# Serial_LCD.net
KiCad netlist of a schematic drawn in EAGLE
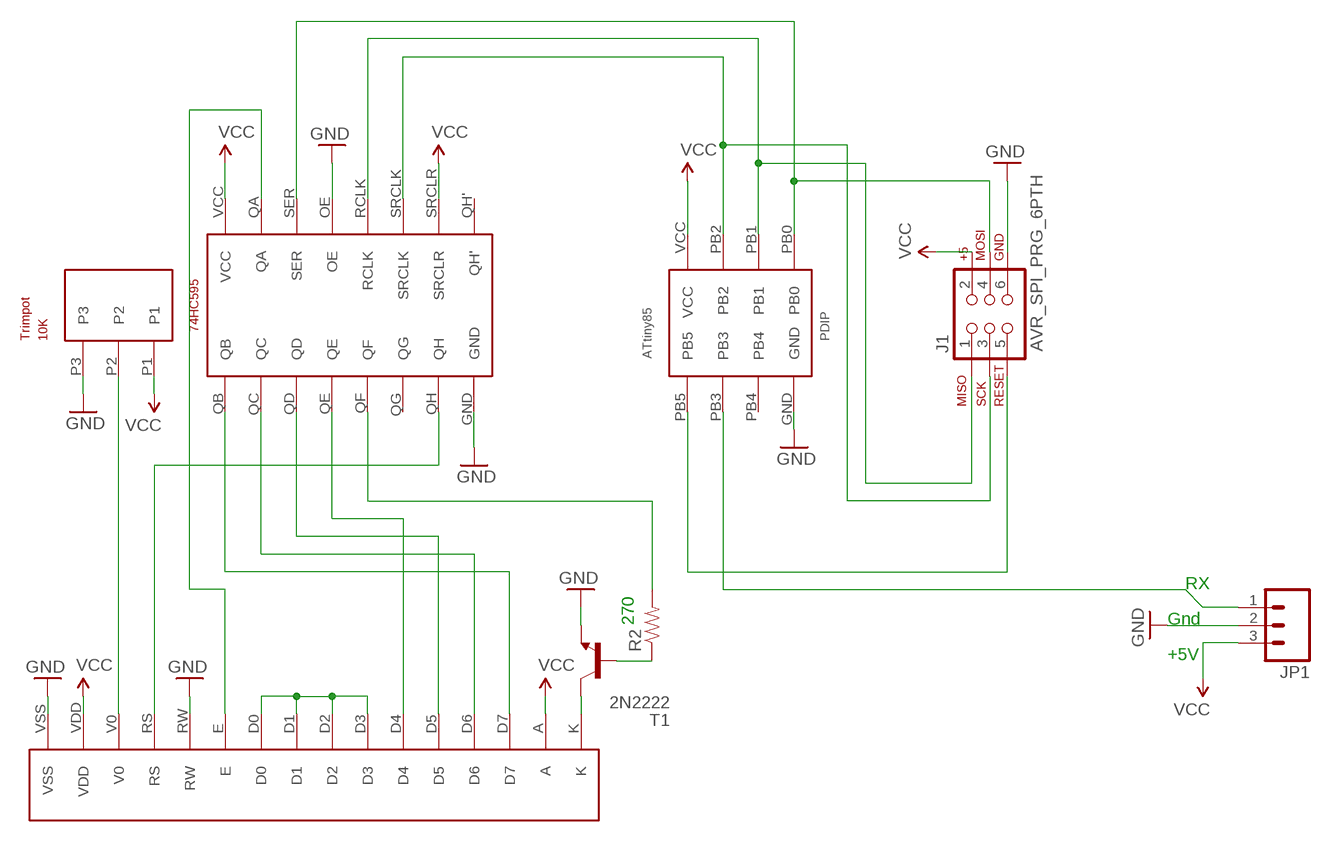
[diagram p0: schematic, sheet 1]

(export (version "E")
  (design (tool "Eeschema 10.0.6"))
  (components
    (comp (ref "J1")
      (value "AVR_SPI_PRG_6PTH")
      (footprint "eagle-import:2X3")
      (libsource (lib "eagle-import") (part "AVR_SPI_PRG_6PTH"))
    )
    (comp (ref "JP1")
      (value "M03PTH")
      (footprint "eagle-import:1X03")
      (libsource (lib "eagle-import") (part "M03PTH"))
    )
    (comp (ref "R1")
      (value "TRIMPOT-3386P")
      (footprint "eagle-import:TRIMPOT-3386P")
      (libsource (lib "eagle-import") (part "TRIMPOT-3386P"))
    )
    (comp (ref "R2")
      (value "RESISTORPTH-1/4W")
      (footprint "eagle-import:AXIAL-0.4")
      (libsource (lib "eagle-import") (part "RESISTORPTH-1/4W"))
    )
    (comp (ref "T1")
      (value "2N2222")
      (footprint "eagle-import:TO92-EBC-OVAL")
      (libsource (lib "eagle-import") (part "2N2222"))
    )
    (comp (ref "U$1")
      (value "16X2_LCD")
      (footprint "eagle-import:16X2_LCD")
      (libsource (lib "eagle-import") (part "16X2_LCD"))
    )
    (comp (ref "U1")
      (value "SN74HC595N")
      (footprint "eagle-import:SN74HC595N")
      (libsource (lib "eagle-import") (part "SN74HC595N"))
    )
    (comp (ref "U2")
      (value "ATTINY85-20PU")
      (footprint "eagle-import:ATTINY85-20PU")
      (libsource (lib "eagle-import") (part "ATTINY85-20PU"))
    )
  )
  (nets
    (net (code "1") (name "GND") (class "Default")
      (node (ref "J1") (pin "6") (pinfunction "6_6") (pintype "passive"))
      (node (ref "JP1") (pin "2") (pinfunction "2_2") (pintype "passive"))
      (node (ref "R1") (pin "P3") (pinfunction "P3_P3") (pintype "bidirectional"))
      (node (ref "T1") (pin "E") (pinfunction "E_E") (pintype "passive"))
      (node (ref "U$1") (pin "RW") (pinfunction "RW_RW") (pintype "bidirectional"))
      (node (ref "U$1") (pin "VSS") (pinfunction "VSS_VSS") (pintype "bidirectional"))
      (node (ref "U1") (pin "GND") (pinfunction "GND_GND") (pintype "power_in"))
      (node (ref "U1") (pin "OE") (pinfunction "OE_OE") (pintype "input"))
      (node (ref "U2") (pin "GND") (pinfunction "GND_GND") (pintype "power_in"))
    )
    (net (code "2") (name "Net-(J1-Pad1)") (class "Default")
      (node (ref "J1") (pin "1") (pinfunction "1_1") (pintype "passive"))
      (node (ref "U1") (pin "RCLK") (pinfunction "RCLK_RCLK") (pintype "input"))
      (node (ref "U2") (pin "PB1") (pinfunction "PB1_PB1") (pintype "bidirectional"))
    )
    (net (code "3") (name "Net-(J1-Pad3)") (class "Default")
      (node (ref "J1") (pin "3") (pinfunction "3_3") (pintype "passive"))
      (node (ref "U1") (pin "SRCLK") (pinfunction "SRCLK_SRCLK") (pintype "input"))
      (node (ref "U2") (pin "PB2") (pinfunction "PB2_PB2") (pintype "bidirectional"))
    )
    (net (code "4") (name "Net-(J1-Pad4)") (class "Default")
      (node (ref "J1") (pin "4") (pinfunction "4_4") (pintype "passive"))
      (node (ref "U1") (pin "SER") (pinfunction "SER_SER") (pintype "input"))
      (node (ref "U2") (pin "PB0") (pinfunction "PB0_PB0") (pintype "bidirectional"))
    )
    (net (code "5") (name "Net-(J1-Pad5)") (class "Default")
      (node (ref "J1") (pin "5") (pinfunction "5_5") (pintype "passive"))
      (node (ref "U2") (pin "PB5") (pinfunction "PB5_PB5") (pintype "bidirectional"))
    )
    (net (code "6") (name "Net-(JP1-Pad1)") (class "Default")
      (node (ref "JP1") (pin "1") (pinfunction "1_1") (pintype "passive"))
      (node (ref "U2") (pin "PB3") (pinfunction "PB3_PB3") (pintype "bidirectional"))
    )
    (net (code "7") (name "Net-(R1-PadP2)") (class "Default")
      (node (ref "R1") (pin "P2") (pinfunction "P2_P2") (pintype "bidirectional"))
      (node (ref "U$1") (pin "V0") (pinfunction "V0_V0") (pintype "bidirectional"))
    )
    (net (code "8") (name "Net-(R2-1)") (class "Default")
      (node (ref "R2") (pin "P$1") (pinfunction "1_P$1") (pintype "passive"))
      (node (ref "T1") (pin "B") (pinfunction "B_B") (pintype "passive"))
    )
    (net (code "9") (name "Net-(R2-2)") (class "Default")
      (node (ref "R2") (pin "P$2") (pinfunction "2_P$2") (pintype "passive"))
      (node (ref "U1") (pin "QF") (pinfunction "QF_QF") (pintype "output"))
    )
    (net (code "10") (name "Net-(T1-PadC)") (class "Default")
      (node (ref "T1") (pin "C") (pinfunction "C_C") (pintype "passive"))
      (node (ref "U$1") (pin "K") (pinfunction "K_K") (pintype "bidirectional"))
    )
    (net (code "11") (name "Net-(U$1-PadD0)") (class "Default")
      (node (ref "U$1") (pin "D0") (pinfunction "D0_D0") (pintype "bidirectional"))
      (node (ref "U$1") (pin "D1") (pinfunction "D1_D1") (pintype "bidirectional"))
      (node (ref "U$1") (pin "D2") (pinfunction "D2_D2") (pintype "bidirectional"))
      (node (ref "U$1") (pin "D3") (pinfunction "D3_D3") (pintype "bidirectional"))
    )
    (net (code "12") (name "Net-(U$1-PadD4)") (class "Default")
      (node (ref "U$1") (pin "D4") (pinfunction "D4_D4") (pintype "bidirectional"))
      (node (ref "U1") (pin "QE") (pinfunction "QE_QE") (pintype "output"))
    )
    (net (code "13") (name "Net-(U$1-PadD5)") (class "Default")
      (node (ref "U$1") (pin "D5") (pinfunction "D5_D5") (pintype "bidirectional"))
      (node (ref "U1") (pin "QD") (pinfunction "QD_QD") (pintype "output"))
    )
    (net (code "14") (name "Net-(U$1-PadD6)") (class "Default")
      (node (ref "U$1") (pin "D6") (pinfunction "D6_D6") (pintype "bidirectional"))
      (node (ref "U1") (pin "QC") (pinfunction "QC_QC") (pintype "output"))
    )
    (net (code "15") (name "Net-(U$1-PadD7)") (class "Default")
      (node (ref "U$1") (pin "D7") (pinfunction "D7_D7") (pintype "bidirectional"))
      (node (ref "U1") (pin "QB") (pinfunction "QB_QB") (pintype "output"))
    )
    (net (code "16") (name "Net-(U$1-PadE)") (class "Default")
      (node (ref "U$1") (pin "E") (pinfunction "E_E") (pintype "bidirectional"))
      (node (ref "U1") (pin "QA") (pinfunction "QA_QA") (pintype "output"))
    )
    (net (code "17") (name "Net-(U$1-PadRS)") (class "Default")
      (node (ref "U$1") (pin "RS") (pinfunction "RS_RS") (pintype "bidirectional"))
      (node (ref "U1") (pin "QH") (pinfunction "QH_QH") (pintype "output"))
    )
    (net (code "18") (name "VCC") (class "Default")
      (node (ref "J1") (pin "2") (pinfunction "2_2") (pintype "passive"))
      (node (ref "JP1") (pin "3") (pinfunction "3_3") (pintype "passive"))
      (node (ref "R1") (pin "P1") (pinfunction "P1_P1") (pintype "bidirectional"))
      (node (ref "U$1") (pin "A") (pinfunction "A_A") (pintype "bidirectional"))
      (node (ref "U$1") (pin "VDD") (pinfunction "VDD_VDD") (pintype "bidirectional"))
      (node (ref "U1") (pin "SRCLR") (pinfunction "SRCLR_SRCLR") (pintype "input"))
      (node (ref "U1") (pin "VCC") (pinfunction "VCC_VCC") (pintype "power_in"))
      (node (ref "U2") (pin "VCC") (pinfunction "VCC_VCC") (pintype "power_in"))
    )
    (net (code "19") (name "unconnected-(U1-PadQG)") (class "Default")
      (node (ref "U1") (pin "QG") (pinfunction "QG_QG") (pintype "output"))
    )
    (net (code "20") (name "unconnected-(U1-PadQH')") (class "Default")
      (node (ref "U1") (pin "QH'") (pinfunction "QH'_QH'") (pintype "output"))
    )
    (net (code "21") (name "unconnected-(U2-PadPB4)") (class "Default")
      (node (ref "U2") (pin "PB4") (pinfunction "PB4_PB4") (pintype "bidirectional"))
    )
  )
)
